# MRsheet.net
KiCad netlist of a schematic drawn in Altium Designer
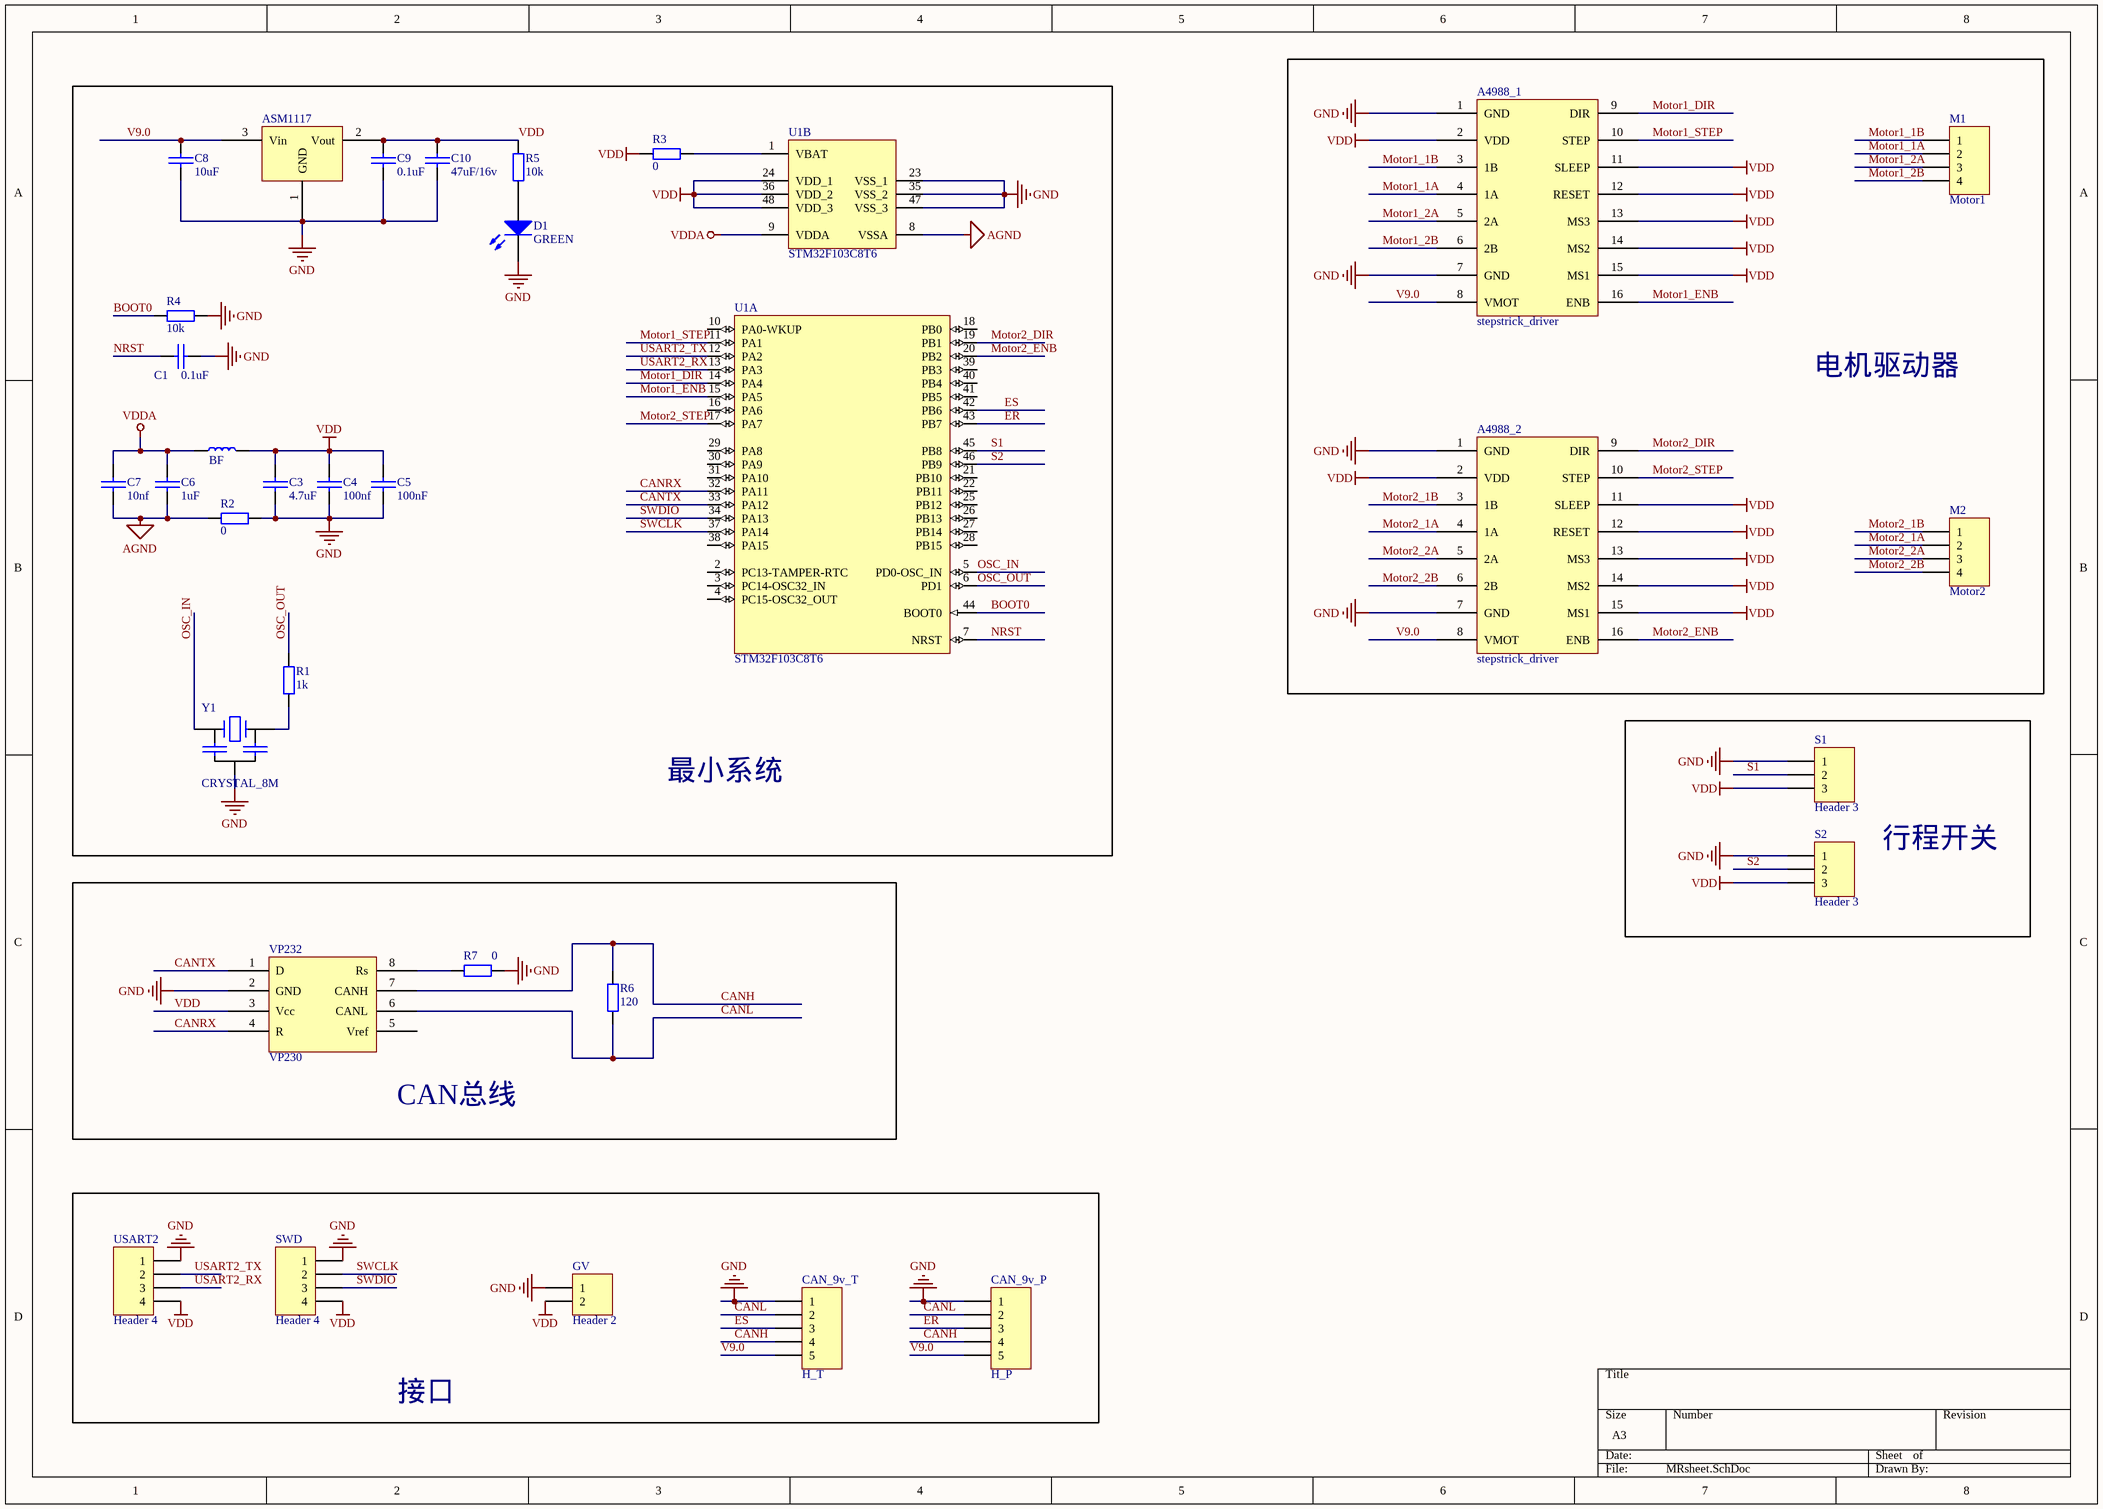
[diagram p0: MRsheet.SchDoc]

(export (version "E")
  (design (tool "Eeschema 10.0.6"))
  (components
    (comp (ref "A4988_1")
      (value "stepstrick_driver")
      (footprint "A4988")
      (libsource (lib "ZYX") (part "stepstrick_driver"))
    )
    (comp (ref "A4988_2")
      (value "stepstrick_driver")
      (footprint "A4988")
      (libsource (lib "ZYX") (part "stepstrick_driver"))
    )
    (comp (ref "ASM1117") (value "ASM1117") (footprint "SOT223") (libsource (lib "ZYX") (part "ASM1117")))
    (comp (ref "BF")
      (value "BF")
      (footprint "R1608[0603]")
      (description "磁珠")
      (libsource (lib "SkyWorks2") (part "BF"))
    )
    (comp (ref "C1")
      (value "0.1uF")
      (footprint "C1608[0603]N")
      (description "贴片无极性电容")
      (fields (field (name "Comment") "cap smd"))
      (libsource (lib "SkyWorks") (part "CAP"))
    )
    (comp (ref "C3")
      (value "4.7uF")
      (footprint "C1608[0603]N")
      (description "贴片无极性电容")
      (fields (field (name "Comment") "cap smd"))
      (libsource (lib "SkyWorks2") (part "CAP"))
    )
    (comp (ref "C4")
      (value "100nf")
      (footprint "C1608[0603]N")
      (description "贴片无极性电容")
      (fields (field (name "Comment") "cap smd"))
      (libsource (lib "SkyWorks2") (part "CAP"))
    )
    (comp (ref "C5")
      (value "100nF")
      (footprint "C1608[0603]N")
      (description "贴片无极性电容")
      (fields (field (name "Comment") "cap smd"))
      (libsource (lib "SkyWorks2") (part "CAP"))
    )
    (comp (ref "C6")
      (value "1uF")
      (footprint "C1608[0603]N")
      (description "贴片无极性电容")
      (fields (field (name "Comment") "cap smd"))
      (libsource (lib "SkyWorks2") (part "CAP"))
    )
    (comp (ref "C7")
      (value "10nf")
      (footprint "C1608[0603]N")
      (description "贴片无极性电容")
      (fields (field (name "Comment") "cap smd"))
      (libsource (lib "SkyWorks2") (part "CAP"))
    )
    (comp (ref "C8")
      (value "10uF")
      (footprint "C1608[0603]N")
      (description "贴片无极性电容")
      (fields (field (name "Comment") "cap smd"))
      (libsource (lib "SkyWorks2") (part "CAP"))
    )
    (comp (ref "C9")
      (value "0.1uF")
      (footprint "C1608[0603]N")
      (description "贴片无极性电容")
      (fields (field (name "Comment") "cap smd"))
      (libsource (lib "SkyWorks2") (part "CAP"))
    )
    (comp (ref "C10")
      (value "47uF/16v")
      (footprint "C1608[0603]N")
      (description "贴片无极性电容")
      (fields (field (name "Comment") "cap smd"))
      (libsource (lib "SkyWorks2") (part "CAP"))
    )
    (comp (ref "CAN_9v_P")
      (value "H_P")
      (footprint "HDR1X5")
      (description "Header, 5-Pin")
      (fields (field (name "PUBLISHER") "Altium Limited"))
      (libsource (lib "Miscellaneous Connectors") (part "Header 5"))
    )
    (comp (ref "CAN_9v_T")
      (value "H_T")
      (footprint "HDR1X5")
      (description "Header, 5-Pin")
      (fields (field (name "PUBLISHER") "Altium Limited"))
      (libsource (lib "Miscellaneous Connectors") (part "Header 5"))
    )
    (comp (ref "D1")
      (value "GREEN")
      (footprint "D1608[0603]")
      (description "蓝色 LED")
      (fields (field (name "Comment") "LED") (field (name "PUBLISHER") "Altium Limited"))
      (libsource (lib "SkyWorks") (part "LED"))
    )
    (comp (ref "GV")
      (value "Header 2")
      (footprint "HDR1X2")
      (description "Header, 2-Pin")
      (fields (field (name "PUBLISHER") "Altium Limited"))
      (libsource (lib "Miscellaneous Connectors") (part "Header 2"))
    )
    (comp (ref "M1")
      (value "Motor1")
      (footprint "HDR1X4")
      (description "Header, 4-Pin")
      (fields (field (name "PUBLISHER") "Altium Limited"))
      (libsource (lib "") (part "Header 4_1"))
    )
    (comp (ref "M2")
      (value "Motor2")
      (footprint "HDR1X4")
      (description "Header, 4-Pin")
      (fields (field (name "PUBLISHER") "Altium Limited"))
      (libsource (lib "") (part "Header 4_1"))
    )
    (comp (ref "R1")
      (value "1k")
      (footprint "R1608[0603]")
      (fields (field (name "Comment") "RES1"))
      (libsource (lib "SkyWorks2") (part "RES1"))
    )
    (comp (ref "R2")
      (value "0")
      (footprint "R1608[0603]")
      (fields (field (name "Comment") "RES1"))
      (libsource (lib "SkyWorks2") (part "RES1"))
    )
    (comp (ref "R3")
      (value "0")
      (footprint "1608[0603]")
      (fields (field (name "Comment") "RES1"))
      (libsource (lib "SkyWorks2") (part "RES1"))
    )
    (comp (ref "R4")
      (value "10k")
      (footprint "1608[0603]")
      (fields (field (name "Comment") "RES1"))
      (libsource (lib "SkyWorks") (part "RES1"))
    )
    (comp (ref "R5")
      (value "10k")
      (footprint "R1608[0603]")
      (fields (field (name "Comment") "RES1"))
      (libsource (lib "SkyWorks2") (part "RES1"))
    )
    (comp (ref "R6")
      (value "120")
      (footprint "R1608[0603]")
      (fields (field (name "Comment") "RES1"))
      (libsource (lib "SkyWorks2") (part "RES1"))
    )
    (comp (ref "R7")
      (value "0")
      (footprint "R1608[0603]")
      (fields (field (name "Comment") "RES1"))
      (libsource (lib "SkyWorks2") (part "RES1"))
    )
    (comp (ref "S1")
      (value "Header 3")
      (footprint "HDR1X3")
      (description "Header, 3-Pin")
      (fields (field (name "PUBLISHER") "Altium Limited"))
      (libsource (lib "Miscellaneous Connectors") (part "Header 3"))
    )
    (comp (ref "S2")
      (value "Header 3")
      (footprint "HDR1X3")
      (description "Header, 3-Pin")
      (fields (field (name "PUBLISHER") "Altium Limited"))
      (libsource (lib "Miscellaneous Connectors") (part "Header 3"))
    )
    (comp (ref "SWD")
      (value "Header 4")
      (footprint "HDR1X4")
      (description "Header, 4-Pin")
      (fields (field (name "PUBLISHER") "Altium Limited"))
      (libsource (lib "Miscellaneous Connectors") (part "Header 4"))
    )
    (comp (ref "U1")
      (value "STM32F103C8T6")
      (footprint "STMicroelectronics STM32 F1:STM-LQFP48_N")
      (libsource (lib "STMicroelectronics STM32 F1") (part "STM32F103C8T6"))
    )
    (comp (ref "USART2")
      (value "Header 4")
      (footprint "HDR1X4")
      (description "Header, 4-Pin")
      (fields (field (name "PUBLISHER") "Altium Limited"))
      (libsource (lib "Miscellaneous Connectors") (part "Header 4"))
    )
    (comp (ref "VP232") (value "VP230") (footprint "VP232") (libsource (lib "VP232") (part "Component_1")))
    (comp (ref "Y1")
      (value "CRYSTAL_8M")
      (footprint "Crystal_C")
      (description "Crystal_8M")
      (libsource (lib "SkyWorks2") (part "CRYSTAL_C"))
    )
  )
  (nets
    (net (code "1") (name "/BOOT0") (class "Default")
      (node (ref "R4") (pin "2") (pinfunction "2_2") (pintype "passive"))
      (node (ref "U1") (pin "44") (pinfunction "BOOT0_44") (pintype "input"))
    )
    (net (code "2") (name "/CANH") (class "Default")
      (node (ref "CAN_9v_P") (pin "4") (pinfunction "4_4") (pintype "passive"))
      (node (ref "CAN_9v_T") (pin "4") (pinfunction "4_4") (pintype "passive"))
      (node (ref "R6") (pin "2") (pinfunction "2_2") (pintype "passive"))
      (node (ref "VP232") (pin "7") (pinfunction "CANH_7") (pintype "passive"))
    )
    (net (code "3") (name "/CANL") (class "Default")
      (node (ref "CAN_9v_P") (pin "2") (pinfunction "2_2") (pintype "passive"))
      (node (ref "CAN_9v_T") (pin "2") (pinfunction "2_2") (pintype "passive"))
      (node (ref "R6") (pin "1") (pinfunction "1_1") (pintype "passive"))
      (node (ref "VP232") (pin "6") (pinfunction "CANL_6") (pintype "passive"))
    )
    (net (code "4") (name "/CANRX") (class "Default")
      (node (ref "U1") (pin "32") (pinfunction "PA11_32") (pintype "bidirectional"))
      (node (ref "VP232") (pin "4") (pinfunction "R_4") (pintype "passive"))
    )
    (net (code "5") (name "/CANTX") (class "Default")
      (node (ref "U1") (pin "33") (pinfunction "PA12_33") (pintype "bidirectional"))
      (node (ref "VP232") (pin "1") (pinfunction "D_1") (pintype "passive"))
    )
    (net (code "6") (name "/ER") (class "Default")
      (node (ref "CAN_9v_P") (pin "3") (pinfunction "3_3") (pintype "passive"))
      (node (ref "U1") (pin "43") (pinfunction "PB7_43") (pintype "bidirectional"))
    )
    (net (code "7") (name "/ES") (class "Default")
      (node (ref "CAN_9v_T") (pin "3") (pinfunction "3_3") (pintype "passive"))
      (node (ref "U1") (pin "42") (pinfunction "PB6_42") (pintype "bidirectional"))
    )
    (net (code "8") (name "/Motor1_1A") (class "Default")
      (node (ref "A4988_1") (pin "4") (pinfunction "1A_4") (pintype "passive"))
      (node (ref "M1") (pin "2") (pinfunction "2_2") (pintype "passive"))
    )
    (net (code "9") (name "/Motor1_1B") (class "Default")
      (node (ref "A4988_1") (pin "3") (pinfunction "1B_3") (pintype "passive"))
      (node (ref "M1") (pin "1") (pinfunction "1_1") (pintype "passive"))
    )
    (net (code "10") (name "/Motor1_2A") (class "Default")
      (node (ref "A4988_1") (pin "5") (pinfunction "2A_5") (pintype "passive"))
      (node (ref "M1") (pin "3") (pinfunction "3_3") (pintype "passive"))
    )
    (net (code "11") (name "/Motor1_2B") (class "Default")
      (node (ref "A4988_1") (pin "6") (pinfunction "2B_6") (pintype "passive"))
      (node (ref "M1") (pin "4") (pinfunction "4_4") (pintype "passive"))
    )
    (net (code "12") (name "/Motor1_DIR") (class "Default")
      (node (ref "A4988_1") (pin "9") (pinfunction "DIR_9") (pintype "passive"))
      (node (ref "U1") (pin "14") (pinfunction "PA4_14") (pintype "bidirectional"))
    )
    (net (code "13") (name "/Motor1_ENB") (class "Default")
      (node (ref "A4988_1") (pin "16") (pinfunction "ENB_16") (pintype "passive"))
      (node (ref "U1") (pin "15") (pinfunction "PA5_15") (pintype "bidirectional"))
    )
    (net (code "14") (name "/Motor1_STEP") (class "Default")
      (node (ref "A4988_1") (pin "10") (pinfunction "STEP_10") (pintype "passive"))
      (node (ref "U1") (pin "11") (pinfunction "PA1_11") (pintype "bidirectional"))
    )
    (net (code "15") (name "/Motor2_1A") (class "Default")
      (node (ref "A4988_2") (pin "4") (pinfunction "1A_4") (pintype "passive"))
      (node (ref "M2") (pin "2") (pinfunction "2_2") (pintype "passive"))
    )
    (net (code "16") (name "/Motor2_1B") (class "Default")
      (node (ref "A4988_2") (pin "3") (pinfunction "1B_3") (pintype "passive"))
      (node (ref "M2") (pin "1") (pinfunction "1_1") (pintype "passive"))
    )
    (net (code "17") (name "/Motor2_2A") (class "Default")
      (node (ref "A4988_2") (pin "5") (pinfunction "2A_5") (pintype "passive"))
      (node (ref "M2") (pin "3") (pinfunction "3_3") (pintype "passive"))
    )
    (net (code "18") (name "/Motor2_2B") (class "Default")
      (node (ref "A4988_2") (pin "6") (pinfunction "2B_6") (pintype "passive"))
      (node (ref "M2") (pin "4") (pinfunction "4_4") (pintype "passive"))
    )
    (net (code "19") (name "/Motor2_DIR") (class "Default")
      (node (ref "A4988_2") (pin "9") (pinfunction "DIR_9") (pintype "passive"))
      (node (ref "U1") (pin "19") (pinfunction "PB1_19") (pintype "bidirectional"))
    )
    (net (code "20") (name "/Motor2_ENB") (class "Default")
      (node (ref "A4988_2") (pin "16") (pinfunction "ENB_16") (pintype "passive"))
      (node (ref "U1") (pin "20") (pinfunction "PB2_20") (pintype "bidirectional"))
    )
    (net (code "21") (name "/Motor2_STEP") (class "Default")
      (node (ref "A4988_2") (pin "10") (pinfunction "STEP_10") (pintype "passive"))
      (node (ref "U1") (pin "17") (pinfunction "PA7_17") (pintype "bidirectional"))
    )
    (net (code "22") (name "/NRST") (class "Default")
      (node (ref "C1") (pin "2") (pinfunction "2_2") (pintype "passive"))
      (node (ref "U1") (pin "7") (pinfunction "NRST_7") (pintype "bidirectional"))
    )
    (net (code "23") (name "/OSC_IN") (class "Default")
      (node (ref "U1") (pin "5") (pinfunction "PD0-OSC_IN_5") (pintype "bidirectional"))
      (node (ref "Y1") (pin "1") (pinfunction "1_1") (pintype "passive"))
    )
    (net (code "24") (name "/OSC_OUT") (class "Default")
      (node (ref "R1") (pin "2") (pinfunction "2_2") (pintype "passive"))
      (node (ref "U1") (pin "6") (pinfunction "PD1_6") (pintype "bidirectional"))
    )
    (net (code "25") (name "/S1") (class "Default")
      (node (ref "S1") (pin "2") (pinfunction "2_2") (pintype "passive"))
      (node (ref "U1") (pin "45") (pinfunction "PB8_45") (pintype "bidirectional"))
    )
    (net (code "26") (name "/S2") (class "Default")
      (node (ref "S2") (pin "2") (pinfunction "2_2") (pintype "passive"))
      (node (ref "U1") (pin "46") (pinfunction "PB9_46") (pintype "bidirectional"))
    )
    (net (code "27") (name "/SWCLK") (class "Default")
      (node (ref "SWD") (pin "2") (pinfunction "2_2") (pintype "passive"))
      (node (ref "U1") (pin "37") (pinfunction "PA14_37") (pintype "bidirectional"))
    )
    (net (code "28") (name "/SWDIO") (class "Default")
      (node (ref "SWD") (pin "3") (pinfunction "3_3") (pintype "passive"))
      (node (ref "U1") (pin "34") (pinfunction "PA13_34") (pintype "bidirectional"))
    )
    (net (code "29") (name "/USART2_RX") (class "Default")
      (node (ref "U1") (pin "13") (pinfunction "PA3_13") (pintype "bidirectional"))
      (node (ref "USART2") (pin "3") (pinfunction "3_3") (pintype "passive"))
    )
    (net (code "30") (name "/USART2_TX") (class "Default")
      (node (ref "U1") (pin "12") (pinfunction "PA2_12") (pintype "bidirectional"))
      (node (ref "USART2") (pin "2") (pinfunction "2_2") (pintype "passive"))
    )
    (net (code "31") (name "/V9.0") (class "Default")
      (node (ref "A4988_1") (pin "8") (pinfunction "VMOT_8") (pintype "passive"))
      (node (ref "A4988_2") (pin "8") (pinfunction "VMOT_8") (pintype "passive"))
      (node (ref "ASM1117") (pin "3") (pinfunction "Vin_3") (pintype "passive"))
      (node (ref "C8") (pin "1") (pinfunction "1_1") (pintype "passive"))
      (node (ref "CAN_9v_P") (pin "5") (pinfunction "5_5") (pintype "passive"))
      (node (ref "CAN_9v_T") (pin "5") (pinfunction "5_5") (pintype "passive"))
    )
    (net (code "32") (name "AGND") (class "Default")
      (node (ref "C6") (pin "2") (pinfunction "2_2") (pintype "passive"))
      (node (ref "C7") (pin "2") (pinfunction "2_2") (pintype "passive"))
      (node (ref "R2") (pin "1") (pinfunction "1_1") (pintype "passive"))
      (node (ref "U1") (pin "8") (pinfunction "VSSA_8") (pintype "power_in"))
    )
    (net (code "33") (name "GND") (class "Default")
      (node (ref "A4988_1") (pin "1") (pinfunction "GND_1") (pintype "passive"))
      (node (ref "A4988_1") (pin "7") (pinfunction "GND_7") (pintype "passive"))
      (node (ref "A4988_2") (pin "1") (pinfunction "GND_1") (pintype "passive"))
      (node (ref "A4988_2") (pin "7") (pinfunction "GND_7") (pintype "passive"))
      (node (ref "ASM1117") (pin "1") (pinfunction "GND_1") (pintype "passive"))
      (node (ref "C1") (pin "1") (pinfunction "1_1") (pintype "passive"))
      (node (ref "C10") (pin "2") (pinfunction "2_2") (pintype "passive"))
      (node (ref "C3") (pin "2") (pinfunction "2_2") (pintype "passive"))
      (node (ref "C4") (pin "2") (pinfunction "2_2") (pintype "passive"))
      (node (ref "C5") (pin "2") (pinfunction "2_2") (pintype "passive"))
      (node (ref "C8") (pin "2") (pinfunction "2_2") (pintype "passive"))
      (node (ref "C9") (pin "2") (pinfunction "2_2") (pintype "passive"))
      (node (ref "CAN_9v_P") (pin "1") (pinfunction "1_1") (pintype "passive"))
      (node (ref "CAN_9v_T") (pin "1") (pinfunction "1_1") (pintype "passive"))
      (node (ref "D1") (pin "2") (pinfunction "K_2") (pintype "passive"))
      (node (ref "GV") (pin "1") (pinfunction "1_1") (pintype "passive"))
      (node (ref "R2") (pin "2") (pinfunction "2_2") (pintype "passive"))
      (node (ref "R4") (pin "1") (pinfunction "1_1") (pintype "passive"))
      (node (ref "R7") (pin "2") (pinfunction "2_2") (pintype "passive"))
      (node (ref "S1") (pin "1") (pinfunction "1_1") (pintype "passive"))
      (node (ref "S2") (pin "1") (pinfunction "1_1") (pintype "passive"))
      (node (ref "SWD") (pin "1") (pinfunction "1_1") (pintype "passive"))
      (node (ref "U1") (pin "23") (pinfunction "VSS_1_23") (pintype "power_in"))
      (node (ref "U1") (pin "35") (pinfunction "VSS_2_35") (pintype "power_in"))
      (node (ref "U1") (pin "47") (pinfunction "VSS_3_47") (pintype "power_in"))
      (node (ref "USART2") (pin "1") (pinfunction "1_1") (pintype "passive"))
      (node (ref "VP232") (pin "2") (pinfunction "GND_2") (pintype "passive"))
      (node (ref "Y1") (pin "2") (pinfunction "GND_2") (pintype "passive"))
    )
    (net (code "34") (name "Net-(D1-A)") (class "Default")
      (node (ref "D1") (pin "1") (pinfunction "A_1") (pintype "passive"))
      (node (ref "R5") (pin "1") (pinfunction "1_1") (pintype "passive"))
    )
    (net (code "35") (name "Net-(R1-Pad1)") (class "Default")
      (node (ref "R1") (pin "1") (pinfunction "1_1") (pintype "passive"))
      (node (ref "Y1") (pin "3") (pinfunction "3_3") (pintype "passive"))
    )
    (net (code "36") (name "Net-(U1B-VBAT)") (class "Default")
      (node (ref "R3") (pin "2") (pinfunction "2_2") (pintype "passive"))
      (node (ref "U1") (pin "1") (pinfunction "VBAT_1") (pintype "power_in"))
    )
    (net (code "37") (name "Net-(VP232-Rs)") (class "Default")
      (node (ref "R7") (pin "1") (pinfunction "1_1") (pintype "passive"))
      (node (ref "VP232") (pin "8") (pinfunction "Rs_8") (pintype "passive"))
    )
    (net (code "38") (name "VDD") (class "Default")
      (node (ref "A4988_1") (pin "11") (pinfunction "SLEEP_11") (pintype "passive"))
      (node (ref "A4988_1") (pin "12") (pinfunction "RESET_12") (pintype "passive"))
      (node (ref "A4988_1") (pin "13") (pinfunction "MS3_13") (pintype "passive"))
      (node (ref "A4988_1") (pin "14") (pinfunction "MS2_14") (pintype "passive"))
      (node (ref "A4988_1") (pin "15") (pinfunction "MS1_15") (pintype "passive"))
      (node (ref "A4988_1") (pin "2") (pinfunction "VDD_2") (pintype "passive"))
      (node (ref "A4988_2") (pin "11") (pinfunction "SLEEP_11") (pintype "passive"))
      (node (ref "A4988_2") (pin "12") (pinfunction "RESET_12") (pintype "passive"))
      (node (ref "A4988_2") (pin "13") (pinfunction "MS3_13") (pintype "passive"))
      (node (ref "A4988_2") (pin "14") (pinfunction "MS2_14") (pintype "passive"))
      (node (ref "A4988_2") (pin "15") (pinfunction "MS1_15") (pintype "passive"))
      (node (ref "A4988_2") (pin "2") (pinfunction "VDD_2") (pintype "passive"))
      (node (ref "ASM1117") (pin "2") (pinfunction "Vout_2") (pintype "passive"))
      (node (ref "BF") (pin "2") (pinfunction "2_2") (pintype "passive"))
      (node (ref "C10") (pin "1") (pinfunction "1_1") (pintype "passive"))
      (node (ref "C3") (pin "1") (pinfunction "1_1") (pintype "passive"))
      (node (ref "C4") (pin "1") (pinfunction "1_1") (pintype "passive"))
      (node (ref "C5") (pin "1") (pinfunction "1_1") (pintype "passive"))
      (node (ref "C9") (pin "1") (pinfunction "1_1") (pintype "passive"))
      (node (ref "GV") (pin "2") (pinfunction "2_2") (pintype "passive"))
      (node (ref "R3") (pin "1") (pinfunction "1_1") (pintype "passive"))
      (node (ref "R5") (pin "2") (pinfunction "2_2") (pintype "passive"))
      (node (ref "S1") (pin "3") (pinfunction "3_3") (pintype "passive"))
      (node (ref "S2") (pin "3") (pinfunction "3_3") (pintype "passive"))
      (node (ref "SWD") (pin "4") (pinfunction "4_4") (pintype "passive"))
      (node (ref "U1") (pin "24") (pinfunction "VDD_1_24") (pintype "power_in"))
      (node (ref "U1") (pin "36") (pinfunction "VDD_2_36") (pintype "power_in"))
      (node (ref "U1") (pin "48") (pinfunction "VDD_3_48") (pintype "power_in"))
      (node (ref "USART2") (pin "4") (pinfunction "4_4") (pintype "passive"))
      (node (ref "VP232") (pin "3") (pinfunction "Vcc_3") (pintype "passive"))
    )
    (net (code "39") (name "VDDA") (class "Default")
      (node (ref "BF") (pin "1") (pinfunction "1_1") (pintype "passive"))
      (node (ref "C6") (pin "1") (pinfunction "1_1") (pintype "passive"))
      (node (ref "C7") (pin "1") (pinfunction "1_1") (pintype "passive"))
      (node (ref "U1") (pin "9") (pinfunction "VDDA_9") (pintype "power_in"))
    )
    (net (code "40") (name "unconnected-(U1A-PA0-WKUP-Pad10)") (class "Default")
      (node (ref "U1") (pin "10") (pinfunction "PA0-WKUP_10") (pintype "bidirectional"))
    )
    (net (code "41") (name "unconnected-(U1A-PA6-Pad16)") (class "Default")
      (node (ref "U1") (pin "16") (pinfunction "PA6_16") (pintype "bidirectional"))
    )
    (net (code "42") (name "unconnected-(U1A-PA8-Pad29)") (class "Default")
      (node (ref "U1") (pin "29") (pinfunction "PA8_29") (pintype "bidirectional"))
    )
    (net (code "43") (name "unconnected-(U1A-PA9-Pad30)") (class "Default")
      (node (ref "U1") (pin "30") (pinfunction "PA9_30") (pintype "bidirectional"))
    )
    (net (code "44") (name "unconnected-(U1A-PA10-Pad31)") (class "Default")
      (node (ref "U1") (pin "31") (pinfunction "PA10_31") (pintype "bidirectional"))
    )
    (net (code "45") (name "unconnected-(U1A-PA15-Pad38)") (class "Default")
      (node (ref "U1") (pin "38") (pinfunction "PA15_38") (pintype "bidirectional"))
    )
    (net (code "46") (name "unconnected-(U1A-PB0-Pad18)") (class "Default")
      (node (ref "U1") (pin "18") (pinfunction "PB0_18") (pintype "bidirectional"))
    )
    (net (code "47") (name "unconnected-(U1A-PB3-Pad39)") (class "Default")
      (node (ref "U1") (pin "39") (pinfunction "PB3_39") (pintype "bidirectional"))
    )
    (net (code "48") (name "unconnected-(U1A-PB4-Pad40)") (class "Default")
      (node (ref "U1") (pin "40") (pinfunction "PB4_40") (pintype "bidirectional"))
    )
    (net (code "49") (name "unconnected-(U1A-PB5-Pad41)") (class "Default")
      (node (ref "U1") (pin "41") (pinfunction "PB5_41") (pintype "bidirectional"))
    )
    (net (code "50") (name "unconnected-(U1A-PB10-Pad21)") (class "Default")
      (node (ref "U1") (pin "21") (pinfunction "PB10_21") (pintype "bidirectional"))
    )
    (net (code "51") (name "unconnected-(U1A-PB11-Pad22)") (class "Default")
      (node (ref "U1") (pin "22") (pinfunction "PB11_22") (pintype "bidirectional"))
    )
    (net (code "52") (name "unconnected-(U1A-PB12-Pad25)") (class "Default")
      (node (ref "U1") (pin "25") (pinfunction "PB12_25") (pintype "bidirectional"))
    )
    (net (code "53") (name "unconnected-(U1A-PB13-Pad26)") (class "Default")
      (node (ref "U1") (pin "26") (pinfunction "PB13_26") (pintype "bidirectional"))
    )
    (net (code "54") (name "unconnected-(U1A-PB14-Pad27)") (class "Default")
      (node (ref "U1") (pin "27") (pinfunction "PB14_27") (pintype "bidirectional"))
    )
    (net (code "55") (name "unconnected-(U1A-PB15-Pad28)") (class "Default")
      (node (ref "U1") (pin "28") (pinfunction "PB15_28") (pintype "bidirectional"))
    )
    (net (code "56") (name "unconnected-(U1A-PC13-TAMPER-RTC-Pad2)") (class "Default")
      (node (ref "U1") (pin "2") (pinfunction "PC13-TAMPER-RTC_2") (pintype "bidirectional"))
    )
    (net (code "57") (name "unconnected-(U1A-PC14-OSC32_IN-Pad3)") (class "Default")
      (node (ref "U1") (pin "3") (pinfunction "PC14-OSC32_IN_3") (pintype "bidirectional"))
    )
    (net (code "58") (name "unconnected-(U1A-PC15-OSC32_OUT-Pad4)") (class "Default")
      (node (ref "U1") (pin "4") (pinfunction "PC15-OSC32_OUT_4") (pintype "bidirectional"))
    )
    (net (code "59") (name "unconnected-(VP232-Vref-Pad5)") (class "Default")
      (node (ref "VP232") (pin "5") (pinfunction "Vref_5") (pintype "passive"))
    )
  )
)
